# Conn_pcb.net
KiCad netlist of a schematic drawn in EAGLE
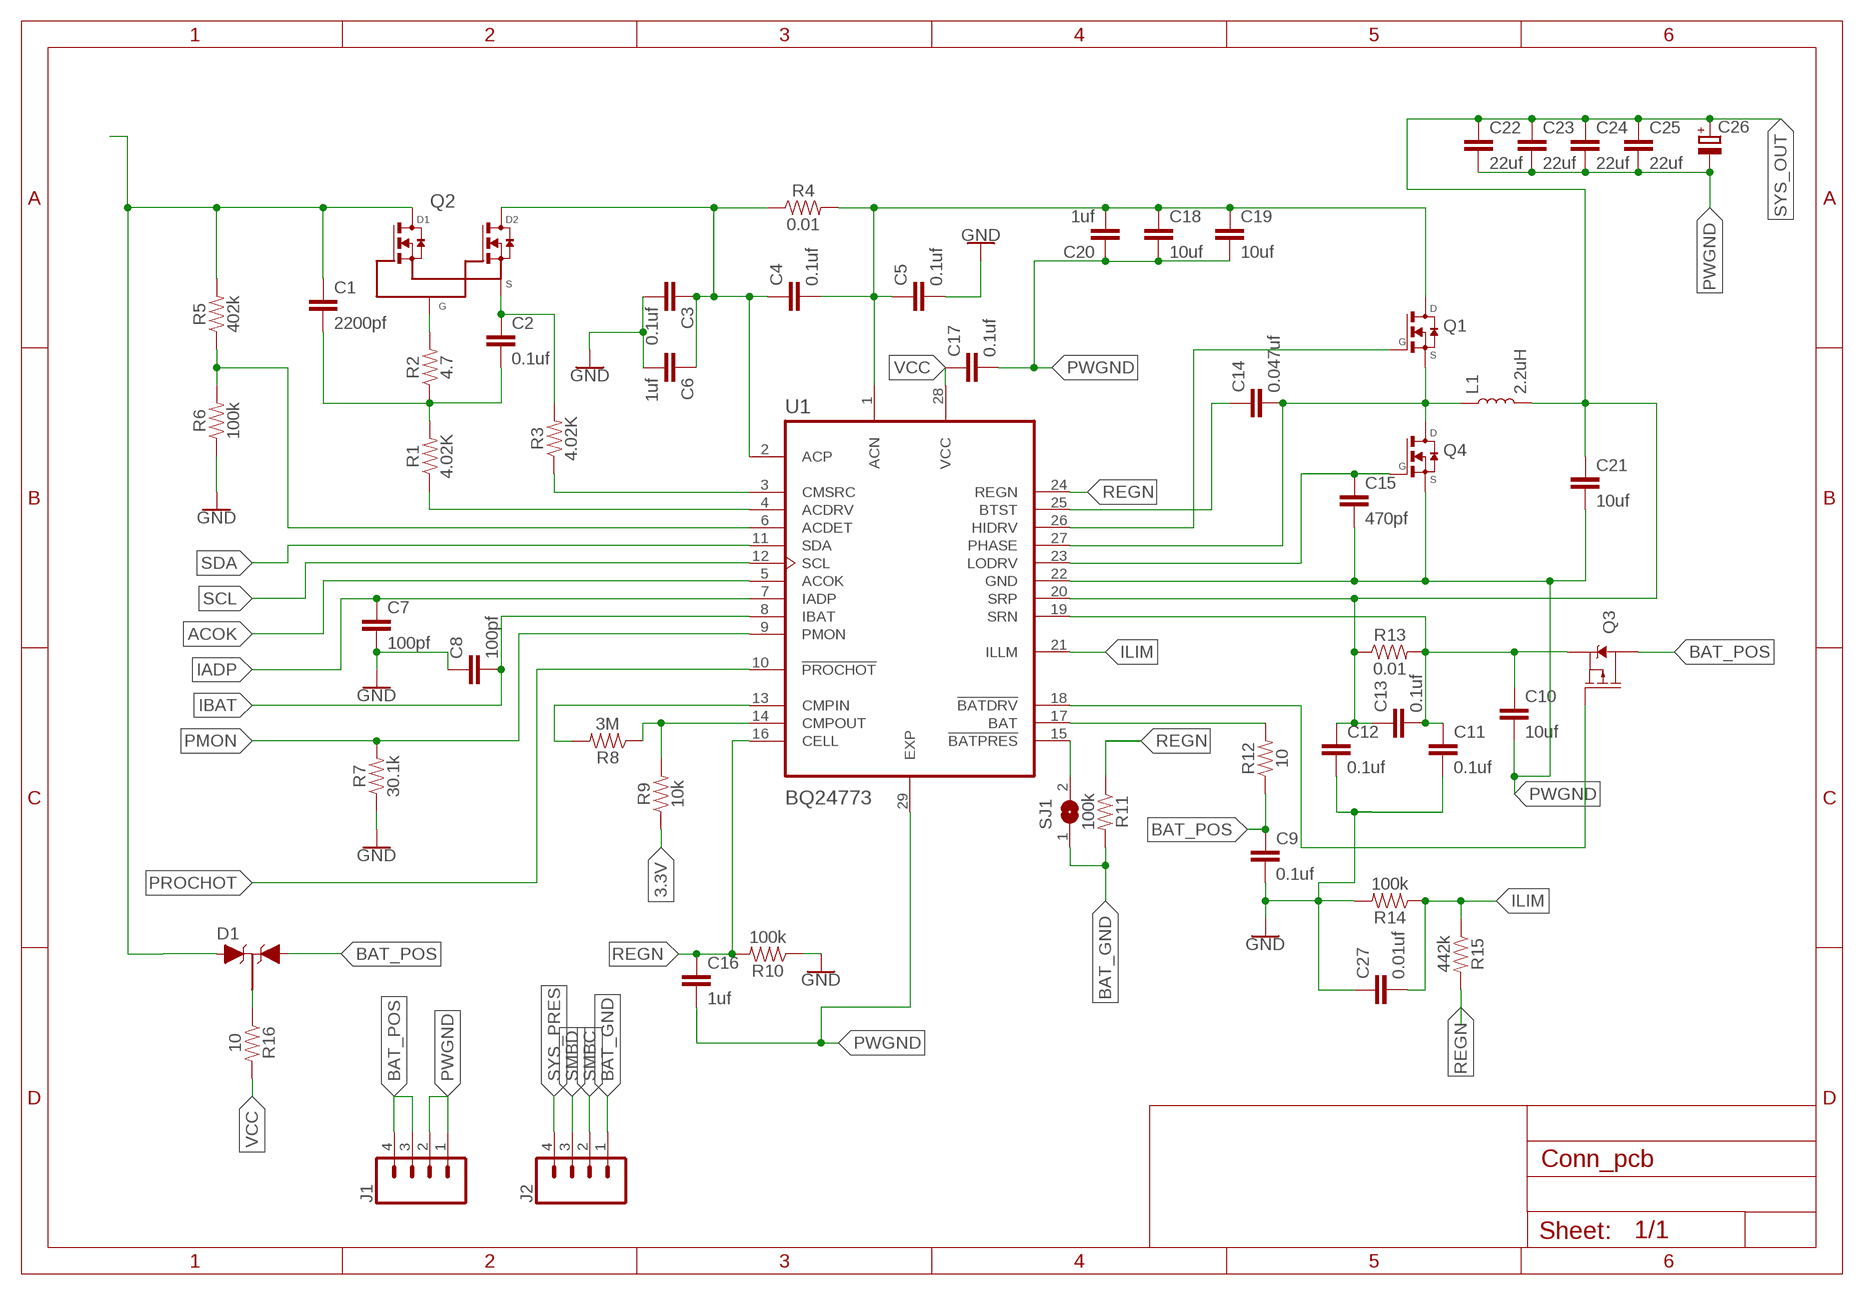
[diagram p0: schematic, sheet 1]

(export (version "E")
  (design (tool "Eeschema 10.0.6"))
  (components
    (comp (ref "C1")
      (value "2200pf")
      (footprint "eagle-import:CAPC1005X50")
      (libsource (lib "eagle-import") (part "CAP0402"))
    )
    (comp (ref "C2")
      (value "0.1uf")
      (footprint "eagle-import:CAPC1005X50")
      (libsource (lib "eagle-import") (part "CAP0402"))
    )
    (comp (ref "C3")
      (value "0.1uf")
      (footprint "eagle-import:CAPC1005X50")
      (libsource (lib "eagle-import") (part "CAP0402"))
    )
    (comp (ref "C4")
      (value "0.1uf")
      (footprint "eagle-import:CAPC1005X50")
      (libsource (lib "eagle-import") (part "CAP0402"))
    )
    (comp (ref "C5")
      (value "0.1uf")
      (footprint "eagle-import:CAPC1005X50")
      (libsource (lib "eagle-import") (part "CAP0402"))
    )
    (comp (ref "C6")
      (value "1uf")
      (footprint "eagle-import:CAPC1005X50")
      (libsource (lib "eagle-import") (part "CAP0402"))
    )
    (comp (ref "C7")
      (value "100pf")
      (footprint "eagle-import:CAPC1005X50")
      (libsource (lib "eagle-import") (part "CAP0402"))
    )
    (comp (ref "C8")
      (value "100pf")
      (footprint "eagle-import:CAPC1005X50")
      (libsource (lib "eagle-import") (part "CAP0402"))
    )
    (comp (ref "C9")
      (value "0.1uf")
      (footprint "eagle-import:CAPC1005X50")
      (libsource (lib "eagle-import") (part "CAP0402"))
    )
    (comp (ref "C10")
      (value "10uf")
      (footprint "eagle-import:C0805K")
      (libsource (lib "eagle-import") (part "C-EUC0805K"))
    )
    (comp (ref "C11")
      (value "0.1uf")
      (footprint "eagle-import:CAPC1005X50")
      (libsource (lib "eagle-import") (part "CAP0402"))
    )
    (comp (ref "C12")
      (value "0.1uf")
      (footprint "eagle-import:CAPC1005X50")
      (libsource (lib "eagle-import") (part "CAP0402"))
    )
    (comp (ref "C13")
      (value "0.1uf")
      (footprint "eagle-import:CAPC1005X50")
      (libsource (lib "eagle-import") (part "CAP0402"))
    )
    (comp (ref "C14")
      (value "0.047uf")
      (footprint "eagle-import:CAPC1005X50")
      (libsource (lib "eagle-import") (part "CAP0402"))
    )
    (comp (ref "C15")
      (value "470pf")
      (footprint "eagle-import:CAPC1005X50")
      (libsource (lib "eagle-import") (part "CAP0402"))
    )
    (comp (ref "C16")
      (value "1uf")
      (footprint "eagle-import:CAPC1005X50")
      (libsource (lib "eagle-import") (part "CAP0402"))
    )
    (comp (ref "C17")
      (value "0.1uf")
      (footprint "eagle-import:CAPC1005X50")
      (libsource (lib "eagle-import") (part "CAP0402"))
    )
    (comp (ref "C18")
      (value "10uf")
      (footprint "eagle-import:C0805K")
      (libsource (lib "eagle-import") (part "C-EUC0805K"))
    )
    (comp (ref "C19")
      (value "10uf")
      (footprint "eagle-import:C0805K")
      (libsource (lib "eagle-import") (part "C-EUC0805K"))
    )
    (comp (ref "C20")
      (value "1uf")
      (footprint "eagle-import:CAPC1005X50")
      (libsource (lib "eagle-import") (part "CAP0402"))
    )
    (comp (ref "C21")
      (value "10uf")
      (footprint "eagle-import:C0805K")
      (libsource (lib "eagle-import") (part "C-EUC0805K"))
    )
    (comp (ref "C22")
      (value "22uf")
      (footprint "eagle-import:C1206")
      (libsource (lib "eagle-import") (part "C-EUC1206"))
    )
    (comp (ref "C23")
      (value "22uf")
      (footprint "eagle-import:C1206")
      (libsource (lib "eagle-import") (part "C-EUC1206"))
    )
    (comp (ref "C24")
      (value "22uf")
      (footprint "eagle-import:C1206")
      (libsource (lib "eagle-import") (part "C-EUC1206"))
    )
    (comp (ref "C25")
      (value "22uf")
      (footprint "eagle-import:C1206")
      (libsource (lib "eagle-import") (part "C-EUC1206"))
    )
    (comp (ref "C26")
      (value "CPOL-EUF")
      (footprint "eagle-import:PANASONIC_F")
      (libsource (lib "eagle-import") (part "CPOL-EUF"))
    )
    (comp (ref "C27")
      (value "0.01uf")
      (footprint "eagle-import:CAPC1005X50")
      (libsource (lib "eagle-import") (part "CAP0402"))
    )
    (comp (ref "D1")
      (value "BAT54C-7-F")
      (footprint "eagle-import:SOT95P235X110-3")
      (libsource (lib "eagle-import") (part "BAT54C-7-F"))
    )
    (comp (ref "J1")
      (value "CONN_041.3")
      (footprint "eagle-import:1X04_NO_SILK_1.3")
      (libsource (lib "eagle-import") (part "CONN_041.3"))
    )
    (comp (ref "J2")
      (value "CONN_041.3")
      (footprint "eagle-import:1X04_NO_SILK_1.3")
      (libsource (lib "eagle-import") (part "CONN_041.3"))
    )
    (comp (ref "L1")
      (value "2.2uH")
      (footprint "eagle-import:RESM6365X610")
      (libsource (lib "eagle-import") (part "XEL6060-222MEB"))
    )
    (comp (ref "Q1")
      (value "CSD17308Q3")
      (footprint "eagle-import:SON65P330X330X110-8")
      (fields (field (name "SPICEPREFIX") "Q"))
      (libsource (lib "eagle-import") (part "CSD17308Q3"))
    )
    (comp (ref "Q2")
      (value "CSD87312Q3EVSON")
      (footprint "eagle-import:QFN65P330X330X100-12")
      (libsource (lib "eagle-import") (part "CSD87312Q3EVSON"))
    )
    (comp (ref "Q3")
      (value "CSD25402Q3A")
      (footprint "eagle-import:CSD25402Q3A")
      (libsource (lib "eagle-import") (part "CSD25402Q3A"))
    )
    (comp (ref "Q4")
      (value "CSD17308Q3")
      (footprint "eagle-import:SON65P330X330X110-8")
      (fields (field (name "SPICEPREFIX") "Q"))
      (libsource (lib "eagle-import") (part "CSD17308Q3"))
    )
    (comp (ref "R1")
      (value "4.02K")
      (footprint "eagle-import:0402")
      (libsource (lib "eagle-import") (part "RES4K04020402"))
    )
    (comp (ref "R2")
      (value "4.7")
      (footprint "eagle-import:0402")
      (libsource (lib "eagle-import") (part "RES4K04020402"))
    )
    (comp (ref "R3")
      (value "4.02K")
      (footprint "eagle-import:0402")
      (libsource (lib "eagle-import") (part "RES4K04020402"))
    )
    (comp (ref "R4")
      (value "0.01")
      (footprint "eagle-import:1206")
      (libsource (lib "eagle-import") (part "SENSE-RES"))
    )
    (comp (ref "R5")
      (value "402k")
      (footprint "eagle-import:0402")
      (libsource (lib "eagle-import") (part "RES4K04020402"))
    )
    (comp (ref "R6")
      (value "100k")
      (footprint "eagle-import:0402")
      (libsource (lib "eagle-import") (part "RES4K04020402"))
    )
    (comp (ref "R7")
      (value "30.1k")
      (footprint "eagle-import:0402")
      (libsource (lib "eagle-import") (part "RES4K04020402"))
    )
    (comp (ref "R8")
      (value "3M")
      (footprint "eagle-import:0402")
      (libsource (lib "eagle-import") (part "RES4K04020402"))
    )
    (comp (ref "R9")
      (value "10k")
      (footprint "eagle-import:0402")
      (libsource (lib "eagle-import") (part "RES4K04020402"))
    )
    (comp (ref "R10")
      (value "100k")
      (footprint "eagle-import:0402")
      (libsource (lib "eagle-import") (part "RES4K04020402"))
    )
    (comp (ref "R11")
      (value "100k")
      (footprint "eagle-import:0402")
      (libsource (lib "eagle-import") (part "RES4K04020402"))
    )
    (comp (ref "R12")
      (value "10")
      (footprint "eagle-import:0402")
      (libsource (lib "eagle-import") (part "RES4K04020402"))
    )
    (comp (ref "R13")
      (value "0.01")
      (footprint "eagle-import:1206")
      (libsource (lib "eagle-import") (part "SENSE-RES"))
    )
    (comp (ref "R14")
      (value "100k")
      (footprint "eagle-import:0402")
      (libsource (lib "eagle-import") (part "RES4K04020402"))
    )
    (comp (ref "R15")
      (value "442k")
      (footprint "eagle-import:0402")
      (libsource (lib "eagle-import") (part "RES4K04020402"))
    )
    (comp (ref "R16")
      (value "10")
      (footprint "eagle-import:0402")
      (libsource (lib "eagle-import") (part "RES4K04020402"))
    )
    (comp (ref "SJ1") (value "SJ") (footprint "eagle-import:SJ") (libsource (lib "eagle-import") (part "SJ")))
    (comp (ref "U1")
      (value "BQ24773")
      (footprint "eagle-import:QFN40P400X400X80-29T240")
      (libsource (lib "eagle-import") (part "BQ24773"))
    )
  )
  (nets
    (net (code "1") (name "3.3V") (class "Default")
      (node (ref "R9") (pin "1") (pinfunction "1_1") (pintype "passive"))
    )
    (net (code "2") (name "ACOK") (class "Default")
      (node (ref "U1") (pin "5") (pinfunction "ACOK_5") (pintype "output"))
    )
    (net (code "3") (name "BAT_GND") (class "Default")
      (node (ref "J2") (pin "1") (pinfunction "1_1") (pintype "passive"))
      (node (ref "R11") (pin "2") (pinfunction "2_2") (pintype "passive"))
      (node (ref "SJ1") (pin "1") (pinfunction "1_1") (pintype "passive"))
    )
    (net (code "4") (name "BAT_POS") (class "Default")
      (node (ref "C9") (pin "1") (pinfunction "1_1") (pintype "passive"))
      (node (ref "D1") (pin "2") (pinfunction "A2_2") (pintype "passive"))
      (node (ref "J1") (pin "3") (pinfunction "3_3") (pintype "passive"))
      (node (ref "J1") (pin "4") (pinfunction "4_4") (pintype "passive"))
      (node (ref "Q3") (pin "1") (pinfunction "D_1") (pintype "bidirectional"))
      (node (ref "Q3") (pin "2") (pinfunction "D_2") (pintype "bidirectional"))
      (node (ref "Q3") (pin "3") (pinfunction "D_3") (pintype "bidirectional"))
      (node (ref "R12") (pin "1") (pinfunction "1_1") (pintype "passive"))
    )
    (net (code "5") (name "GND") (class "Default")
      (node (ref "C11") (pin "2") (pinfunction "2_2") (pintype "passive"))
      (node (ref "C12") (pin "2") (pinfunction "2_2") (pintype "passive"))
      (node (ref "C27") (pin "1") (pinfunction "1_1") (pintype "passive"))
      (node (ref "C3") (pin "2") (pinfunction "2_2") (pintype "passive"))
      (node (ref "C5") (pin "2") (pinfunction "2_2") (pintype "passive"))
      (node (ref "C6") (pin "2") (pinfunction "2_2") (pintype "passive"))
      (node (ref "C7") (pin "2") (pinfunction "2_2") (pintype "passive"))
      (node (ref "C8") (pin "1") (pinfunction "1_1") (pintype "passive"))
      (node (ref "C9") (pin "2") (pinfunction "2_2") (pintype "passive"))
      (node (ref "R10") (pin "1") (pinfunction "1_1") (pintype "passive"))
      (node (ref "R14") (pin "2") (pinfunction "2_2") (pintype "passive"))
      (node (ref "R6") (pin "1") (pinfunction "1_1") (pintype "passive"))
      (node (ref "R7") (pin "1") (pinfunction "1_1") (pintype "passive"))
    )
    (net (code "6") (name "IADP") (class "Default")
      (node (ref "C7") (pin "1") (pinfunction "1_1") (pintype "passive"))
      (node (ref "U1") (pin "7") (pinfunction "IADP_7") (pintype "output"))
    )
    (net (code "7") (name "IBAT") (class "Default")
      (node (ref "C8") (pin "2") (pinfunction "2_2") (pintype "passive"))
      (node (ref "U1") (pin "8") (pinfunction "IBAT_8") (pintype "output"))
    )
    (net (code "8") (name "ILIM") (class "Default")
      (node (ref "C27") (pin "2") (pinfunction "2_2") (pintype "passive"))
      (node (ref "R14") (pin "1") (pinfunction "1_1") (pintype "passive"))
      (node (ref "R15") (pin "1") (pinfunction "1_1") (pintype "passive"))
      (node (ref "U1") (pin "21") (pinfunction "ILLM_21") (pintype "input"))
    )
    (net (code "9") (name "Net-(C1-Pad2)") (class "Default")
      (node (ref "C1") (pin "2") (pinfunction "2_2") (pintype "passive"))
      (node (ref "C2") (pin "2") (pinfunction "2_2") (pintype "passive"))
      (node (ref "R1") (pin "2") (pinfunction "2_2") (pintype "passive"))
      (node (ref "R2") (pin "1") (pinfunction "1_1") (pintype "passive"))
    )
    (net (code "10") (name "Net-(C2-Pad1)") (class "Default")
      (node (ref "C2") (pin "1") (pinfunction "1_1") (pintype "passive"))
      (node (ref "Q2") (pin "9") (pinfunction "S_9") (pintype "passive"))
      (node (ref "Q2") (pin "9.1") (pinfunction "S_9.1") (pintype "passive"))
      (node (ref "Q2") (pin "9.2") (pinfunction "S_9.2") (pintype "passive"))
      (node (ref "Q2") (pin "9.3") (pinfunction "S_9.3") (pintype "passive"))
      (node (ref "Q2") (pin "9.4") (pinfunction "S_9.4") (pintype "passive"))
      (node (ref "R3") (pin "2") (pinfunction "2_2") (pintype "passive"))
    )
    (net (code "11") (name "Net-(D1-A1)") (class "Default")
      (node (ref "C1") (pin "1") (pinfunction "1_1") (pintype "passive"))
      (node (ref "D1") (pin "1") (pinfunction "A1_1") (pintype "passive"))
      (node (ref "Q2") (pin "1") (pinfunction "D1_1") (pintype "passive"))
      (node (ref "Q2") (pin "3") (pinfunction "D1_3") (pintype "passive"))
      (node (ref "Q2") (pin "4") (pinfunction "D1_4") (pintype "passive"))
      (node (ref "R5") (pin "2") (pinfunction "2_2") (pintype "passive"))
    )
    (net (code "12") (name "Net-(D1-K)") (class "Default")
      (node (ref "D1") (pin "3") (pinfunction "K_3") (pintype "passive"))
      (node (ref "R16") (pin "1") (pinfunction "1_1") (pintype "passive"))
    )
    (net (code "13") (name "Net-(Q1-G)") (class "Default")
      (node (ref "Q1") (pin "4") (pinfunction "G_4") (pintype "passive"))
      (node (ref "U1") (pin "26") (pinfunction "HIDRV_26") (pintype "output"))
    )
    (net (code "14") (name "Net-(Q2-G)") (class "Default")
      (node (ref "Q2") (pin "5") (pinfunction "G_5") (pintype "passive"))
      (node (ref "R2") (pin "2") (pinfunction "2_2") (pintype "passive"))
    )
    (net (code "15") (name "Net-(Q3-G)") (class "Default")
      (node (ref "Q3") (pin "4") (pinfunction "G_4") (pintype "bidirectional"))
      (node (ref "U1") (pin "18") (pinfunction "~{BATDRV}_18") (pintype "output"))
    )
    (net (code "16") (name "Net-(Q4-G)") (class "Default")
      (node (ref "C15") (pin "1") (pinfunction "1_1") (pintype "passive"))
      (node (ref "Q4") (pin "4") (pinfunction "G_4") (pintype "passive"))
      (node (ref "U1") (pin "23") (pinfunction "LODRV_23") (pintype "output"))
    )
    (net (code "17") (name "Net-(U1-ACDET)") (class "Default")
      (node (ref "R5") (pin "1") (pinfunction "1_1") (pintype "passive"))
      (node (ref "R6") (pin "2") (pinfunction "2_2") (pintype "passive"))
      (node (ref "U1") (pin "6") (pinfunction "ACDET_6") (pintype "input"))
    )
    (net (code "18") (name "Net-(U1-ACDRV)") (class "Default")
      (node (ref "R1") (pin "1") (pinfunction "1_1") (pintype "passive"))
      (node (ref "U1") (pin "4") (pinfunction "ACDRV_4") (pintype "output"))
    )
    (net (code "19") (name "Net-(U1-ACN)") (class "Default")
      (node (ref "C18") (pin "1") (pinfunction "1_1") (pintype "passive"))
      (node (ref "C19") (pin "1") (pinfunction "1_1") (pintype "passive"))
      (node (ref "C20") (pin "2") (pinfunction "2_2") (pintype "passive"))
      (node (ref "C4") (pin "2") (pinfunction "2_2") (pintype "passive"))
      (node (ref "C5") (pin "1") (pinfunction "1_1") (pintype "passive"))
      (node (ref "Q1") (pin "5") (pinfunction "D_5") (pintype "passive"))
      (node (ref "Q1") (pin "6") (pinfunction "D_6") (pintype "passive"))
      (node (ref "Q1") (pin "7") (pinfunction "D_7") (pintype "passive"))
      (node (ref "Q1") (pin "8") (pinfunction "D_8") (pintype "passive"))
      (node (ref "R4") (pin "2") (pinfunction "2_2") (pintype "passive"))
      (node (ref "U1") (pin "1") (pinfunction "ACN_1") (pintype "input"))
    )
    (net (code "20") (name "Net-(U1-ACP)") (class "Default")
      (node (ref "C3") (pin "1") (pinfunction "1_1") (pintype "passive"))
      (node (ref "C4") (pin "1") (pinfunction "1_1") (pintype "passive"))
      (node (ref "C6") (pin "1") (pinfunction "1_1") (pintype "passive"))
      (node (ref "Q2") (pin "6") (pinfunction "D2_6") (pintype "passive"))
      (node (ref "Q2") (pin "7") (pinfunction "D2_7") (pintype "passive"))
      (node (ref "Q2") (pin "8") (pinfunction "D2_8") (pintype "passive"))
      (node (ref "R4") (pin "1") (pinfunction "1_1") (pintype "passive"))
      (node (ref "U1") (pin "2") (pinfunction "ACP_2") (pintype "input"))
    )
    (net (code "21") (name "Net-(U1-BAT)") (class "Default")
      (node (ref "R12") (pin "2") (pinfunction "2_2") (pintype "passive"))
      (node (ref "U1") (pin "17") (pinfunction "BAT_17") (pintype "input"))
    )
    (net (code "22") (name "Net-(U1-BTST)") (class "Default")
      (node (ref "C14") (pin "1") (pinfunction "1_1") (pintype "passive"))
      (node (ref "U1") (pin "25") (pinfunction "BTST_25") (pintype "passive"))
    )
    (net (code "23") (name "Net-(U1-CMPIN)") (class "Default")
      (node (ref "R8") (pin "2") (pinfunction "2_2") (pintype "passive"))
      (node (ref "U1") (pin "13") (pinfunction "CMPIN_13") (pintype "input"))
    )
    (net (code "24") (name "Net-(U1-CMPOUT)") (class "Default")
      (node (ref "R8") (pin "1") (pinfunction "1_1") (pintype "passive"))
      (node (ref "R9") (pin "2") (pinfunction "2_2") (pintype "passive"))
      (node (ref "U1") (pin "14") (pinfunction "CMPOUT_14") (pintype "output"))
    )
    (net (code "25") (name "Net-(U1-CMSRC)") (class "Default")
      (node (ref "R3") (pin "1") (pinfunction "1_1") (pintype "passive"))
      (node (ref "U1") (pin "3") (pinfunction "CMSRC_3") (pintype "input"))
    )
    (net (code "26") (name "Net-(U1-PHASE)") (class "Default")
      (node (ref "C14") (pin "2") (pinfunction "2_2") (pintype "passive"))
      (node (ref "L1") (pin "1") (pinfunction "1_1") (pintype "passive"))
      (node (ref "Q1") (pin "1") (pinfunction "S_1") (pintype "passive"))
      (node (ref "Q1") (pin "2") (pinfunction "S_2") (pintype "passive"))
      (node (ref "Q1") (pin "3") (pinfunction "S_3") (pintype "passive"))
      (node (ref "Q4") (pin "5") (pinfunction "D_5") (pintype "passive"))
      (node (ref "Q4") (pin "6") (pinfunction "D_6") (pintype "passive"))
      (node (ref "Q4") (pin "7") (pinfunction "D_7") (pintype "passive"))
      (node (ref "Q4") (pin "8") (pinfunction "D_8") (pintype "passive"))
      (node (ref "U1") (pin "27") (pinfunction "PHASE_27") (pintype "output"))
    )
    (net (code "27") (name "Net-(U1-SRN)") (class "Default")
      (node (ref "C10") (pin "1") (pinfunction "1_1") (pintype "passive"))
      (node (ref "C11") (pin "1") (pinfunction "1_1") (pintype "passive"))
      (node (ref "C13") (pin "2") (pinfunction "2_2") (pintype "passive"))
      (node (ref "Q3") (pin "5") (pinfunction "S_5") (pintype "bidirectional"))
      (node (ref "Q3") (pin "6") (pinfunction "S_6") (pintype "bidirectional"))
      (node (ref "Q3") (pin "7") (pinfunction "S_7") (pintype "bidirectional"))
      (node (ref "Q3") (pin "8") (pinfunction "S_8") (pintype "bidirectional"))
      (node (ref "Q3") (pin "9") (pinfunction "S_9") (pintype "bidirectional"))
      (node (ref "R13") (pin "2") (pinfunction "2_2") (pintype "passive"))
      (node (ref "U1") (pin "19") (pinfunction "SRN_19") (pintype "input"))
    )
    (net (code "28") (name "Net-(U1-~{BATPRES})") (class "Default")
      (node (ref "SJ1") (pin "2") (pinfunction "2_2") (pintype "passive"))
      (node (ref "U1") (pin "15") (pinfunction "~{BATPRES}_15") (pintype "input"))
    )
    (net (code "29") (name "PMON") (class "Default")
      (node (ref "R7") (pin "2") (pinfunction "2_2") (pintype "passive"))
      (node (ref "U1") (pin "9") (pinfunction "PMON_9") (pintype "output"))
    )
    (net (code "30") (name "PROCHOT") (class "Default")
      (node (ref "U1") (pin "10") (pinfunction "~{PROCHOT}_10") (pintype "output"))
    )
    (net (code "31") (name "PWGND") (class "Default")
      (node (ref "C10") (pin "2") (pinfunction "2_2") (pintype "passive"))
      (node (ref "C15") (pin "2") (pinfunction "2_2") (pintype "passive"))
      (node (ref "C16") (pin "2") (pinfunction "2_2") (pintype "passive"))
      (node (ref "C17") (pin "2") (pinfunction "2_2") (pintype "passive"))
      (node (ref "C18") (pin "2") (pinfunction "2_2") (pintype "passive"))
      (node (ref "C19") (pin "2") (pinfunction "2_2") (pintype "passive"))
      (node (ref "C20") (pin "1") (pinfunction "1_1") (pintype "passive"))
      (node (ref "C21") (pin "2") (pinfunction "2_2") (pintype "passive"))
      (node (ref "C22") (pin "2") (pinfunction "2_2") (pintype "passive"))
      (node (ref "C23") (pin "2") (pinfunction "2_2") (pintype "passive"))
      (node (ref "C24") (pin "2") (pinfunction "2_2") (pintype "passive"))
      (node (ref "C25") (pin "2") (pinfunction "2_2") (pintype "passive"))
      (node (ref "C26") (pin "-") (pinfunction "-_-") (pintype "passive"))
      (node (ref "J1") (pin "1") (pinfunction "1_1") (pintype "passive"))
      (node (ref "J1") (pin "2") (pinfunction "2_2") (pintype "passive"))
      (node (ref "Q4") (pin "1") (pinfunction "S_1") (pintype "passive"))
      (node (ref "Q4") (pin "2") (pinfunction "S_2") (pintype "passive"))
      (node (ref "Q4") (pin "3") (pinfunction "S_3") (pintype "passive"))
      (node (ref "U1") (pin "22") (pinfunction "GND_22") (pintype "power_in"))
      (node (ref "U1") (pin "29") (pinfunction "EXP_29") (pintype "power_in"))
    )
    (net (code "32") (name "REGN") (class "Default")
      (node (ref "C16") (pin "1") (pinfunction "1_1") (pintype "passive"))
      (node (ref "R10") (pin "2") (pinfunction "2_2") (pintype "passive"))
      (node (ref "R11") (pin "1") (pinfunction "1_1") (pintype "passive"))
      (node (ref "R15") (pin "2") (pinfunction "2_2") (pintype "passive"))
      (node (ref "U1") (pin "16") (pinfunction "CELL_16") (pintype "input"))
      (node (ref "U1") (pin "24") (pinfunction "REGN_24") (pintype "output"))
    )
    (net (code "33") (name "SCL") (class "Default")
      (node (ref "U1") (pin "12") (pinfunction "SCL_12") (pintype "input"))
    )
    (net (code "34") (name "SDA") (class "Default")
      (node (ref "U1") (pin "11") (pinfunction "SDA_11") (pintype "bidirectional"))
    )
    (net (code "35") (name "SMBC") (class "Default")
      (node (ref "J2") (pin "2") (pinfunction "2_2") (pintype "passive"))
    )
    (net (code "36") (name "SMBD") (class "Default")
      (node (ref "J2") (pin "3") (pinfunction "3_3") (pintype "passive"))
    )
    (net (code "37") (name "SYS_OUT") (class "Default")
      (node (ref "C12") (pin "1") (pinfunction "1_1") (pintype "passive"))
      (node (ref "C13") (pin "1") (pinfunction "1_1") (pintype "passive"))
      (node (ref "C21") (pin "1") (pinfunction "1_1") (pintype "passive"))
      (node (ref "C22") (pin "1") (pinfunction "1_1") (pintype "passive"))
      (node (ref "C23") (pin "1") (pinfunction "1_1") (pintype "passive"))
      (node (ref "C24") (pin "1") (pinfunction "1_1") (pintype "passive"))
      (node (ref "C25") (pin "1") (pinfunction "1_1") (pintype "passive"))
      (node (ref "C26") (pin "+") (pinfunction "+_+") (pintype "passive"))
      (node (ref "L1") (pin "2") (pinfunction "2_2") (pintype "passive"))
      (node (ref "R13") (pin "1") (pinfunction "1_1") (pintype "passive"))
      (node (ref "U1") (pin "20") (pinfunction "SRP_20") (pintype "input"))
    )
    (net (code "38") (name "SYS_PRES") (class "Default")
      (node (ref "J2") (pin "4") (pinfunction "4_4") (pintype "passive"))
    )
    (net (code "39") (name "VCC") (class "Default")
      (node (ref "C17") (pin "1") (pinfunction "1_1") (pintype "passive"))
      (node (ref "R16") (pin "2") (pinfunction "2_2") (pintype "passive"))
      (node (ref "U1") (pin "28") (pinfunction "VCC_28") (pintype "power_in"))
    )
  )
)
